# CarteMere.net
KiCad netlist of a schematic drawn in Altium Designer
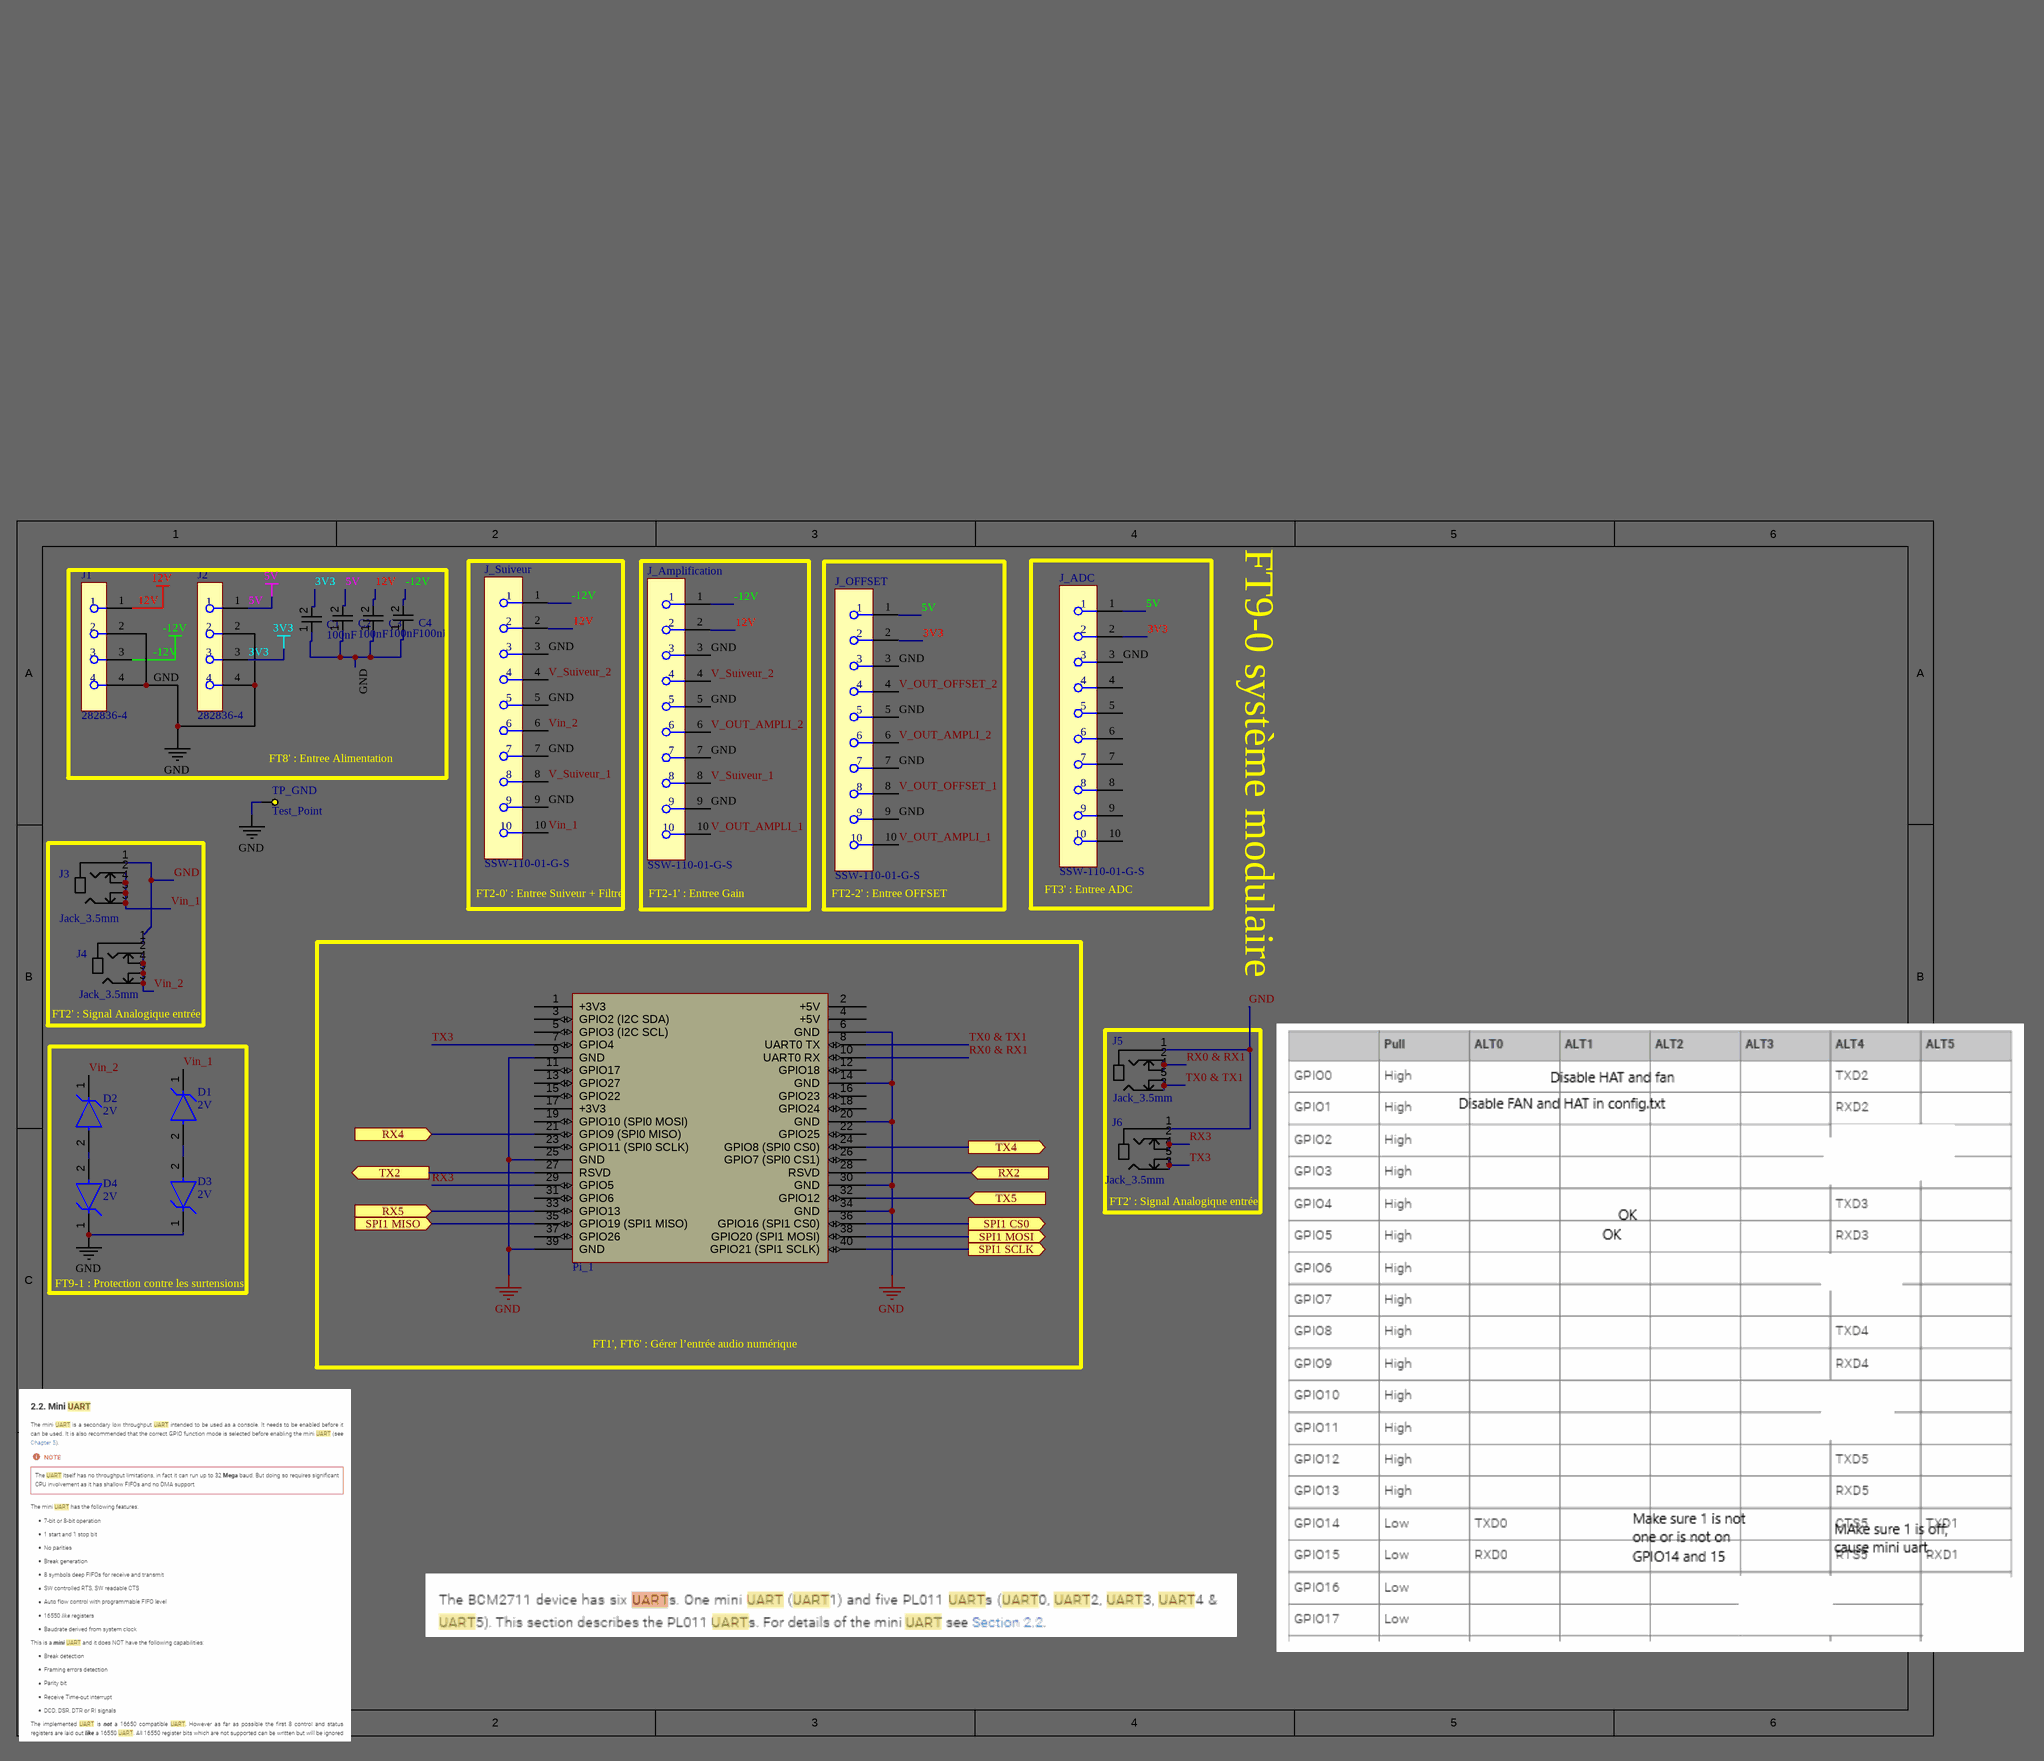
[diagram p0: CarteMere.SchDoc]

(export (version "E")
  (design (tool "Eeschema 10.0.6"))
  (components
    (comp (ref "C1")
      (value "100nF")
      (footprint "PCB:Cap_6.0%2A2.5%2A6mm")
      (fields (field (name "Comment") "Cap_6.0*2.5*6mm"))
      (libsource (lib "Schema") (part "Cap_6.0*2.5*6mm"))
    )
    (comp (ref "C2")
      (value "100nF")
      (footprint "PCB:Cap_6.0%2A2.5%2A6mm")
      (fields (field (name "Comment") "Cap_6.0*2.5*6mm"))
      (libsource (lib "Schema") (part "Cap_6.0*2.5*6mm"))
    )
    (comp (ref "C3")
      (value "100nF")
      (footprint "PCB:Cap_6.0%2A2.5%2A6mm")
      (fields (field (name "Comment") "Cap_6.0*2.5*6mm"))
      (libsource (lib "Schema") (part "Cap_6.0*2.5*6mm"))
    )
    (comp (ref "C4")
      (value "100nF")
      (footprint "PCB:Cap_6.0%2A2.5%2A6mm")
      (fields (field (name "Comment") "Cap_6.0*2.5*6mm"))
      (libsource (lib "Schema") (part "Cap_6.0*2.5*6mm"))
    )
    (comp (ref "D1")
      (value "2V")
      (footprint "PCB:Zener_Diode")
      (fields (field (name "Comment") "ZENER_Diode"))
      (libsource (lib "Schema") (part "ZENER_Diode"))
    )
    (comp (ref "D2")
      (value "2V")
      (footprint "PCB:Zener_Diode")
      (fields (field (name "Comment") "ZENER_Diode"))
      (libsource (lib "Schema") (part "ZENER_Diode"))
    )
    (comp (ref "D3")
      (value "2V")
      (footprint "PCB:Zener_Diode")
      (fields (field (name "Comment") "ZENER_Diode"))
      (libsource (lib "Schema") (part "ZENER_Diode"))
    )
    (comp (ref "D4")
      (value "2V")
      (footprint "PCB:Zener_Diode")
      (fields (field (name "Comment") "ZENER_Diode"))
      (libsource (lib "Schema") (part "ZENER_Diode"))
    )
    (comp (ref "J1")
      (value "282836-4")
      (footprint "FP-282836-4-MFG")
      (description "282836-4 Connector, Terminal Block; Wire Receptacle; 4 Pos.; 16-30 AWG; 0.197 in. CL; Sid")
      (fields (field (name "VOLTAGE") "300V"))
      (libsource (lib "Altium Content Vault") (part "282836-4"))
    )
    (comp (ref "J2")
      (value "282836-4")
      (footprint "FP-282836-4-MFG")
      (description "282836-4 Connector, Terminal Block; Wire Receptacle; 4 Pos.; 16-30 AWG; 0.197 in. CL; Sid")
      (fields (field (name "VOLTAGE") "300V"))
      (libsource (lib "Altium Content Vault") (part "282836-4"))
    )
    (comp (ref "J3")
      (value "Jack_3.5mm")
      (footprint "PCB:Jack_3.5mm_PCB_ 3poles/stereo")
      (description "Connecteur Jack 3,5 mm Prise femelle Lumberg, Montage sur CI")
      (libsource (lib "Schema") (part "Jack_3.5mm_PCB_3pole/stereo"))
    )
    (comp (ref "J4")
      (value "Jack_3.5mm")
      (footprint "PCB:Jack_3.5mm_PCB_ 3poles/stereo")
      (description "Connecteur Jack 3,5 mm Prise femelle Lumberg, Montage sur CI")
      (libsource (lib "Schema") (part "Jack_3.5mm_PCB_3pole/stereo"))
    )
    (comp (ref "J5")
      (value "Jack_3.5mm")
      (footprint "PCB:Jack_3.5mm_PCB_ 3poles/stereo")
      (description "Connecteur Jack 3,5 mm Prise femelle Lumberg, Montage sur CI")
      (libsource (lib "Schema") (part "Jack_3.5mm_PCB_3pole/stereo"))
    )
    (comp (ref "J6")
      (value "Jack_3.5mm")
      (footprint "PCB:Jack_3.5mm_PCB_ 3poles/stereo")
      (description "Connecteur Jack 3,5 mm Prise femelle Lumberg, Montage sur CI")
      (libsource (lib "Schema") (part "Jack_3.5mm_PCB_3pole/stereo"))
    )
    (comp (ref "J_ADC")
      (value "SSW-110-01-G-S")
      (footprint "FP-SSW-110-01-G-S-MFG")
      (libsource (lib "Altium Content Vault") (part "a6b0ccc4a6f32c6729440d11cede569"))
    )
    (comp (ref "J_Amplification")
      (value "SSW-110-01-G-S")
      (footprint "FP-SSW-110-01-G-S-MFG")
      (libsource (lib "Altium Content Vault") (part "a6b0ccc4a6f32c6729440d11cede569"))
    )
    (comp (ref "J_OFFSET")
      (value "SSW-110-01-G-S")
      (footprint "FP-SSW-110-01-G-S-MFG")
      (libsource (lib "Altium Content Vault") (part "a6b0ccc4a6f32c6729440d11cede569"))
    )
    (comp (ref "J_Suiveur")
      (value "SSW-110-01-G-S")
      (footprint "FP-SSW-110-01-G-S-MFG")
      (libsource (lib "Altium Content Vault") (part "a6b0ccc4a6f32c6729440d11cede569"))
    )
    (comp (ref "Pi_1")
      (value "GPIO_conn_RaspberyPi")
      (footprint "PCB:Pi_20x2_pins_Male")
      (libsource (lib "Schema") (part "GPIO_conn_RaspberyPi"))
    )
    (comp (ref "TP_GND")
      (value "Test_Point")
      (footprint "PCB:Test_Point_Hook")
      (libsource (lib "Schema") (part "Test_Point"))
    )
  )
  (nets
    (net (code "1") (name "-12V") (class "Default")
      (node (ref "C4") (pin "2") (pinfunction "2_2") (pintype "passive"))
      (node (ref "J1") (pin "3") (pinfunction "3_3") (pintype "passive"))
      (node (ref "J_Amplification") (pin "1") (pinfunction "1_1") (pintype "passive"))
      (node (ref "J_Suiveur") (pin "1") (pinfunction "1_1") (pintype "passive"))
    )
    (net (code "3") (name "/RX0 & RX1") (class "Default")
      (node (ref "J5") (pin "2") (pinfunction "2_2") (pintype "passive"))
      (node (ref "J5") (pin "4") (pinfunction "4_4") (pintype "passive"))
      (node (ref "Pi_1") (pin "10") (pinfunction "UART0_RX_10") (pintype "bidirectional"))
    )
    (net (code "4") (name "/RX2") (class "Default")
      (node (ref "Pi_1") (pin "28") (pinfunction "RSVD_28") (pintype "passive"))
    )
    (net (code "5") (name "/RX3") (class "Default")
      (node (ref "J6") (pin "2") (pinfunction "2_2") (pintype "passive"))
      (node (ref "J6") (pin "4") (pinfunction "4_4") (pintype "passive"))
      (node (ref "Pi_1") (pin "29") (pinfunction "GPIO5_29") (pintype "bidirectional"))
    )
    (net (code "6") (name "/RX4") (class "Default")
      (node (ref "Pi_1") (pin "21") (pinfunction "GPIO9_(SPI0_MISO)_21") (pintype "bidirectional"))
    )
    (net (code "7") (name "/RX5") (class "Default")
      (node (ref "Pi_1") (pin "33") (pinfunction "GPIO13_33") (pintype "bidirectional"))
    )
    (net (code "8") (name "/SPI1 CS0") (class "Default")
      (node (ref "Pi_1") (pin "36") (pinfunction "GPIO16_(SPI1_CS0)_36") (pintype "bidirectional"))
    )
    (net (code "9") (name "/SPI1 MISO") (class "Default")
      (node (ref "Pi_1") (pin "35") (pinfunction "GPIO19_(SPI1_MISO)_35") (pintype "bidirectional"))
    )
    (net (code "10") (name "/SPI1 MOSI") (class "Default")
      (node (ref "Pi_1") (pin "38") (pinfunction "GPIO20_(SPI1_MOSI)_38") (pintype "bidirectional"))
    )
    (net (code "11") (name "/SPI1 SCLK") (class "Default")
      (node (ref "Pi_1") (pin "40") (pinfunction "GPIO21_(SPI1_SCLK)_40") (pintype "bidirectional"))
    )
    (net (code "12") (name "/TX0 & TX1") (class "Default")
      (node (ref "J5") (pin "3") (pinfunction "3_3") (pintype "passive"))
      (node (ref "J5") (pin "5") (pinfunction "5_5") (pintype "passive"))
      (node (ref "Pi_1") (pin "8") (pinfunction "UART0_TX_8") (pintype "bidirectional"))
    )
    (net (code "13") (name "/TX2") (class "Default")
      (node (ref "Pi_1") (pin "27") (pinfunction "RSVD_27") (pintype "passive"))
    )
    (net (code "14") (name "/TX3") (class "Default")
      (node (ref "J6") (pin "3") (pinfunction "3_3") (pintype "passive"))
      (node (ref "J6") (pin "5") (pinfunction "5_5") (pintype "passive"))
      (node (ref "Pi_1") (pin "7") (pinfunction "GPIO4_7") (pintype "bidirectional"))
    )
    (net (code "15") (name "/TX4") (class "Default")
      (node (ref "Pi_1") (pin "24") (pinfunction "GPIO8_(SPI0_CS0)_24") (pintype "bidirectional"))
    )
    (net (code "16") (name "/TX5") (class "Default")
      (node (ref "Pi_1") (pin "32") (pinfunction "GPIO12_32") (pintype "bidirectional"))
    )
    (net (code "17") (name "/V_OUT_AMPLI_1") (class "Default")
      (node (ref "J_Amplification") (pin "10") (pinfunction "10_10") (pintype "passive"))
      (node (ref "J_OFFSET") (pin "10") (pinfunction "10_10") (pintype "passive"))
    )
    (net (code "18") (name "/V_OUT_AMPLI_2") (class "Default")
      (node (ref "J_Amplification") (pin "6") (pinfunction "6_6") (pintype "passive"))
      (node (ref "J_OFFSET") (pin "6") (pinfunction "6_6") (pintype "passive"))
    )
    (net (code "19") (name "/V_OUT_OFFSET_1") (class "Default")
      (node (ref "J_OFFSET") (pin "8") (pinfunction "8_8") (pintype "passive"))
    )
    (net (code "20") (name "/V_OUT_OFFSET_2") (class "Default")
      (node (ref "J_OFFSET") (pin "4") (pinfunction "4_4") (pintype "passive"))
    )
    (net (code "21") (name "/V_Suiveur_1") (class "Default")
      (node (ref "J_Amplification") (pin "8") (pinfunction "8_8") (pintype "passive"))
      (node (ref "J_Suiveur") (pin "8") (pinfunction "8_8") (pintype "passive"))
    )
    (net (code "22") (name "/V_Suiveur_2") (class "Default")
      (node (ref "J_Amplification") (pin "4") (pinfunction "4_4") (pintype "passive"))
      (node (ref "J_Suiveur") (pin "4") (pinfunction "4_4") (pintype "passive"))
    )
    (net (code "23") (name "/Vin_1") (class "Default")
      (node (ref "D1") (pin "1") (pinfunction "C_1") (pintype "passive"))
      (node (ref "J3") (pin "2") (pinfunction "2_2") (pintype "passive"))
      (node (ref "J3") (pin "3") (pinfunction "3_3") (pintype "passive"))
      (node (ref "J3") (pin "4") (pinfunction "4_4") (pintype "passive"))
      (node (ref "J3") (pin "5") (pinfunction "5_5") (pintype "passive"))
      (node (ref "J_Suiveur") (pin "10") (pinfunction "10_10") (pintype "passive"))
    )
    (net (code "24") (name "/Vin_2") (class "Default")
      (node (ref "D2") (pin "1") (pinfunction "C_1") (pintype "passive"))
      (node (ref "J4") (pin "2") (pinfunction "2_2") (pintype "passive"))
      (node (ref "J4") (pin "3") (pinfunction "3_3") (pintype "passive"))
      (node (ref "J4") (pin "4") (pinfunction "4_4") (pintype "passive"))
      (node (ref "J4") (pin "5") (pinfunction "5_5") (pintype "passive"))
      (node (ref "J_Suiveur") (pin "6") (pinfunction "6_6") (pintype "passive"))
    )
    (net (code "25") (name "3V3") (class "Default")
      (node (ref "C1") (pin "2") (pinfunction "2_2") (pintype "passive"))
      (node (ref "J2") (pin "3") (pinfunction "3_3") (pintype "passive"))
      (node (ref "J_ADC") (pin "2") (pinfunction "2_2") (pintype "passive"))
      (node (ref "J_OFFSET") (pin "2") (pinfunction "2_2") (pintype "passive"))
    )
    (net (code "26") (name "5V") (class "Default")
      (node (ref "C2") (pin "2") (pinfunction "2_2") (pintype "passive"))
      (node (ref "J2") (pin "1") (pinfunction "1_1") (pintype "passive"))
      (node (ref "J_ADC") (pin "1") (pinfunction "1_1") (pintype "passive"))
      (node (ref "J_OFFSET") (pin "1") (pinfunction "1_1") (pintype "passive"))
    )
    (net (code "27") (name "12V") (class "Default")
      (node (ref "C3") (pin "2") (pinfunction "2_2") (pintype "passive"))
      (node (ref "J1") (pin "1") (pinfunction "1_1") (pintype "passive"))
      (node (ref "J_Amplification") (pin "2") (pinfunction "2_2") (pintype "passive"))
      (node (ref "J_Suiveur") (pin "2") (pinfunction "2_2") (pintype "passive"))
    )
    (net (code "28") (name "GND") (class "Default")
      (node (ref "C1") (pin "1") (pinfunction "1_1") (pintype "passive"))
      (node (ref "C2") (pin "1") (pinfunction "1_1") (pintype "passive"))
      (node (ref "C3") (pin "1") (pinfunction "1_1") (pintype "passive"))
      (node (ref "C4") (pin "1") (pinfunction "1_1") (pintype "passive"))
      (node (ref "D3") (pin "1") (pinfunction "C_1") (pintype "passive"))
      (node (ref "D4") (pin "1") (pinfunction "C_1") (pintype "passive"))
      (node (ref "J1") (pin "2") (pinfunction "2_2") (pintype "passive"))
      (node (ref "J1") (pin "4") (pinfunction "4_4") (pintype "passive"))
      (node (ref "J2") (pin "2") (pinfunction "2_2") (pintype "passive"))
      (node (ref "J2") (pin "4") (pinfunction "4_4") (pintype "passive"))
      (node (ref "J3") (pin "1") (pinfunction "1_1") (pintype "passive"))
      (node (ref "J4") (pin "1") (pinfunction "1_1") (pintype "passive"))
      (node (ref "J5") (pin "1") (pinfunction "1_1") (pintype "passive"))
      (node (ref "J6") (pin "1") (pinfunction "1_1") (pintype "passive"))
      (node (ref "J_ADC") (pin "3") (pinfunction "3_3") (pintype "passive"))
      (node (ref "J_Amplification") (pin "3") (pinfunction "3_3") (pintype "passive"))
      (node (ref "J_Amplification") (pin "5") (pinfunction "5_5") (pintype "passive"))
      (node (ref "J_Amplification") (pin "7") (pinfunction "7_7") (pintype "passive"))
      (node (ref "J_Amplification") (pin "9") (pinfunction "9_9") (pintype "passive"))
      (node (ref "J_OFFSET") (pin "3") (pinfunction "3_3") (pintype "passive"))
      (node (ref "J_OFFSET") (pin "5") (pinfunction "5_5") (pintype "passive"))
      (node (ref "J_OFFSET") (pin "7") (pinfunction "7_7") (pintype "passive"))
      (node (ref "J_OFFSET") (pin "9") (pinfunction "9_9") (pintype "passive"))
      (node (ref "J_Suiveur") (pin "3") (pinfunction "3_3") (pintype "passive"))
      (node (ref "J_Suiveur") (pin "5") (pinfunction "5_5") (pintype "passive"))
      (node (ref "J_Suiveur") (pin "7") (pinfunction "7_7") (pintype "passive"))
      (node (ref "J_Suiveur") (pin "9") (pinfunction "9_9") (pintype "passive"))
      (node (ref "Pi_1") (pin "14") (pinfunction "GND_14") (pintype "power_in"))
      (node (ref "Pi_1") (pin "20") (pinfunction "GND_20") (pintype "power_in"))
      (node (ref "Pi_1") (pin "25") (pinfunction "GND_25") (pintype "power_in"))
      (node (ref "Pi_1") (pin "30") (pinfunction "GND_30") (pintype "power_in"))
      (node (ref "Pi_1") (pin "34") (pinfunction "GND_34") (pintype "passive"))
      (node (ref "Pi_1") (pin "39") (pinfunction "GND_39") (pintype "power_in"))
      (node (ref "Pi_1") (pin "6") (pinfunction "GND_6") (pintype "power_in"))
      (node (ref "Pi_1") (pin "9") (pinfunction "GND_9") (pintype "power_in"))
      (node (ref "TP_GND") (pin "Tp?") (pinfunction "0_Tp?") (pintype "passive"))
    )
    (net (code "29") (name "Net-(D1-A)") (class "Default")
      (node (ref "D1") (pin "2") (pinfunction "A_2") (pintype "passive"))
      (node (ref "D3") (pin "2") (pinfunction "A_2") (pintype "passive"))
    )
    (net (code "30") (name "Net-(D2-A)") (class "Default")
      (node (ref "D2") (pin "2") (pinfunction "A_2") (pintype "passive"))
      (node (ref "D4") (pin "2") (pinfunction "A_2") (pintype "passive"))
    )
    (net (code "31") (name "unconnected-(J_ADC-Pad4)") (class "Default")
      (node (ref "J_ADC") (pin "4") (pinfunction "4_4") (pintype "passive"))
    )
    (net (code "32") (name "unconnected-(J_ADC-Pad5)") (class "Default")
      (node (ref "J_ADC") (pin "5") (pinfunction "5_5") (pintype "passive"))
    )
    (net (code "33") (name "unconnected-(J_ADC-Pad6)") (class "Default")
      (node (ref "J_ADC") (pin "6") (pinfunction "6_6") (pintype "passive"))
    )
    (net (code "34") (name "unconnected-(J_ADC-Pad7)") (class "Default")
      (node (ref "J_ADC") (pin "7") (pinfunction "7_7") (pintype "passive"))
    )
    (net (code "35") (name "unconnected-(J_ADC-Pad8)") (class "Default")
      (node (ref "J_ADC") (pin "8") (pinfunction "8_8") (pintype "passive"))
    )
    (net (code "36") (name "unconnected-(J_ADC-Pad9)") (class "Default")
      (node (ref "J_ADC") (pin "9") (pinfunction "9_9") (pintype "passive"))
    )
    (net (code "37") (name "unconnected-(J_ADC-Pad10)") (class "Default")
      (node (ref "J_ADC") (pin "10") (pinfunction "10_10") (pintype "passive"))
    )
    (net (code "38") (name "unconnected-(Pi_1-+3V3-Pad1)") (class "Default")
      (node (ref "Pi_1") (pin "1") (pinfunction "+3V3_1") (pintype "power_in"))
    )
    (net (code "39") (name "unconnected-(Pi_1-+3V3-Pad17)") (class "Default")
      (node (ref "Pi_1") (pin "17") (pinfunction "+3V3_17") (pintype "power_in"))
    )
    (net (code "40") (name "unconnected-(Pi_1-+5V-Pad2)") (class "Default")
      (node (ref "Pi_1") (pin "2") (pinfunction "+5V_2") (pintype "power_in"))
    )
    (net (code "41") (name "unconnected-(Pi_1-+5V-Pad4)") (class "Default")
      (node (ref "Pi_1") (pin "4") (pinfunction "+5V_4") (pintype "power_in"))
    )
    (net (code "42") (name "unconnected-(Pi_1-GPIO2_(I2C_SDA)-Pad3)") (class "Default")
      (node (ref "Pi_1") (pin "3") (pinfunction "GPIO2_(I2C_SDA)_3") (pintype "bidirectional"))
    )
    (net (code "43") (name "unconnected-(Pi_1-GPIO3_(I2C_SCL)-Pad5)") (class "Default")
      (node (ref "Pi_1") (pin "5") (pinfunction "GPIO3_(I2C_SCL)_5") (pintype "bidirectional"))
    )
    (net (code "44") (name "unconnected-(Pi_1-GPIO6-Pad31)") (class "Default")
      (node (ref "Pi_1") (pin "31") (pinfunction "GPIO6_31") (pintype "bidirectional"))
    )
    (net (code "45") (name "unconnected-(Pi_1-GPIO7_(SPI0_CS1)-Pad26)") (class "Default")
      (node (ref "Pi_1") (pin "26") (pinfunction "GPIO7_(SPI0_CS1)_26") (pintype "bidirectional"))
    )
    (net (code "46") (name "unconnected-(Pi_1-GPIO10_(SPI0_MOSI)-Pad19)") (class "Default")
      (node (ref "Pi_1") (pin "19") (pinfunction "GPIO10_(SPI0_MOSI)_19") (pintype "bidirectional"))
    )
    (net (code "47") (name "unconnected-(Pi_1-GPIO11_(SPI0_SCLK)-Pad23)") (class "Default")
      (node (ref "Pi_1") (pin "23") (pinfunction "GPIO11_(SPI0_SCLK)_23") (pintype "bidirectional"))
    )
    (net (code "48") (name "unconnected-(Pi_1-GPIO17-Pad11)") (class "Default")
      (node (ref "Pi_1") (pin "11") (pinfunction "GPIO17_11") (pintype "bidirectional"))
    )
    (net (code "49") (name "unconnected-(Pi_1-GPIO18-Pad12)") (class "Default")
      (node (ref "Pi_1") (pin "12") (pinfunction "GPIO18_12") (pintype "bidirectional"))
    )
    (net (code "50") (name "unconnected-(Pi_1-GPIO22-Pad15)") (class "Default")
      (node (ref "Pi_1") (pin "15") (pinfunction "GPIO22_15") (pintype "bidirectional"))
    )
    (net (code "51") (name "unconnected-(Pi_1-GPIO23-Pad16)") (class "Default")
      (node (ref "Pi_1") (pin "16") (pinfunction "GPIO23_16") (pintype "bidirectional"))
    )
    (net (code "52") (name "unconnected-(Pi_1-GPIO24-Pad18)") (class "Default")
      (node (ref "Pi_1") (pin "18") (pinfunction "GPIO24_18") (pintype "bidirectional"))
    )
    (net (code "53") (name "unconnected-(Pi_1-GPIO25-Pad22)") (class "Default")
      (node (ref "Pi_1") (pin "22") (pinfunction "GPIO25_22") (pintype "bidirectional"))
    )
    (net (code "54") (name "unconnected-(Pi_1-GPIO26-Pad37)") (class "Default")
      (node (ref "Pi_1") (pin "37") (pinfunction "GPIO26_37") (pintype "bidirectional"))
    )
    (net (code "55") (name "unconnected-(Pi_1-GPIO27-Pad13)") (class "Default")
      (node (ref "Pi_1") (pin "13") (pinfunction "GPIO27_13") (pintype "bidirectional"))
    )
  )
)
